# drv.net
KiCad netlist of a schematic drawn in EAGLE
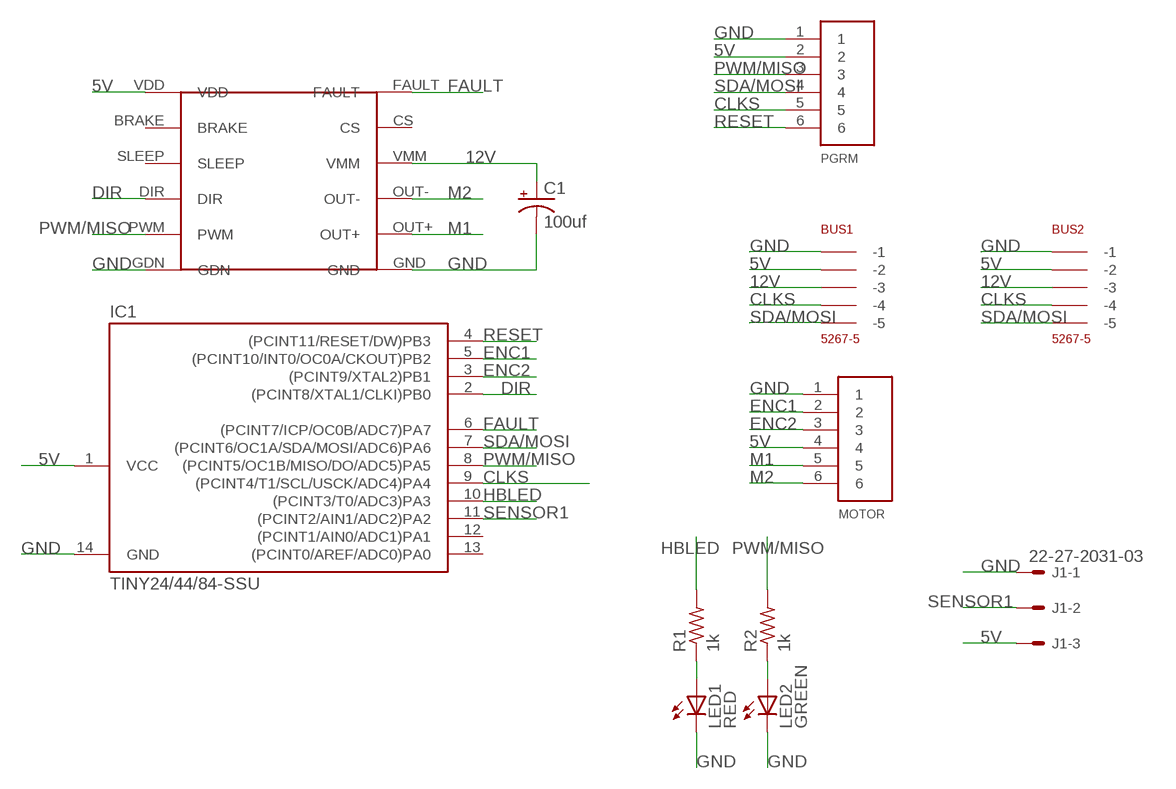
[diagram p0: schematic, sheet 1]

(export (version "E")
  (design (tool "Eeschema 10.0.6"))
  (components
    (comp (ref "BUS1")
      (value "5267-5")
      (footprint "eagle-import:5267-5")
      (libsource (lib "eagle-import") (part "5267-5"))
    )
    (comp (ref "BUS2")
      (value "5267-5")
      (footprint "eagle-import:5267-5")
      (libsource (lib "eagle-import") (part "5267-5"))
    )
    (comp (ref "C1")
      (value "100uf")
      (footprint "eagle-import:E5-10,5")
      (libsource (lib "eagle-import") (part "CPOL-USE5-10.5"))
    )
    (comp (ref "IC1")
      (value "TINY24/44/84-SSU")
      (footprint "eagle-import:SOIC14")
      (libsource (lib "eagle-import") (part "TINY24/44/84-SSU"))
    )
    (comp (ref "J1")
      (value "22-27-2031-03")
      (footprint "eagle-import:6410-03")
      (fields (field (name "MF") "MOLEX"))
      (libsource (lib "eagle-import") (part "22-?-0327-2031"))
    )
    (comp (ref "LED1")
      (value "RED")
      (footprint "eagle-import:1206")
      (libsource (lib "eagle-import") (part "LEDSMT1206"))
    )
    (comp (ref "LED2")
      (value "GREEN")
      (footprint "eagle-import:1206")
      (libsource (lib "eagle-import") (part "LEDSMT1206"))
    )
    (comp (ref "MOTOR")
      (value "6PIN")
      (footprint "eagle-import:B6B-PH-K-S")
      (libsource (lib "eagle-import") (part "6PIN"))
    )
    (comp (ref "PGRM")
      (value "6PIN")
      (footprint "eagle-import:B6B-PH-K-S")
      (libsource (lib "eagle-import") (part "6PIN"))
    )
    (comp (ref "R1")
      (value "1k")
      (footprint "eagle-import:M1206")
      (libsource (lib "eagle-import") (part "R-US_M1206"))
    )
    (comp (ref "R2")
      (value "1k")
      (footprint "eagle-import:M1206")
      (libsource (lib "eagle-import") (part "R-US_M1206"))
    )
    (comp (ref "U$1")
      (value "DRV8801BR")
      (footprint "eagle-import:DRV8801BR")
      (libsource (lib "eagle-import") (part "DRV8801BR"))
    )
  )
  (nets
    (net (code "1") (name "/5V") (class "Default")
      (node (ref "BUS1") (pin "P$2") (pinfunction "-2_P$2") (pintype "bidirectional"))
      (node (ref "BUS2") (pin "P$2") (pinfunction "-2_P$2") (pintype "bidirectional"))
      (node (ref "IC1") (pin "1") (pinfunction "VCC_1") (pintype "power_in"))
      (node (ref "J1") (pin "3") (pinfunction "S_3") (pintype "passive"))
      (node (ref "MOTOR") (pin "4") (pinfunction "4_4") (pintype "bidirectional"))
      (node (ref "PGRM") (pin "2") (pinfunction "2_2") (pintype "bidirectional"))
      (node (ref "U$1") (pin "VDD") (pinfunction "VDD_VDD") (pintype "bidirectional"))
    )
    (net (code "2") (name "/12V") (class "Default")
      (node (ref "BUS1") (pin "P$3") (pinfunction "-3_P$3") (pintype "bidirectional"))
      (node (ref "BUS2") (pin "P$3") (pinfunction "-3_P$3") (pintype "bidirectional"))
      (node (ref "C1") (pin "+") (pinfunction "+_+") (pintype "passive"))
      (node (ref "U$1") (pin "VMM") (pinfunction "VMM_VMM") (pintype "bidirectional"))
    )
    (net (code "3") (name "/CLKS") (class "Default")
      (node (ref "BUS1") (pin "P$4") (pinfunction "-4_P$4") (pintype "bidirectional"))
      (node (ref "BUS2") (pin "P$4") (pinfunction "-4_P$4") (pintype "bidirectional"))
      (node (ref "IC1") (pin "9") (pinfunction "(PCINT4/T1/SCL/USCK/ADC4)PA4_9") (pintype "bidirectional"))
      (node (ref "PGRM") (pin "5") (pinfunction "5_5") (pintype "bidirectional"))
    )
    (net (code "4") (name "/DIR") (class "Default")
      (node (ref "IC1") (pin "2") (pinfunction "(PCINT8/XTAL1/CLKI)PB0_2") (pintype "bidirectional"))
      (node (ref "U$1") (pin "DIR") (pinfunction "DIR_DIR") (pintype "bidirectional"))
    )
    (net (code "5") (name "/ENC1") (class "Default")
      (node (ref "IC1") (pin "5") (pinfunction "(PCINT10/INT0/OC0A/CKOUT)PB2_5") (pintype "bidirectional"))
      (node (ref "MOTOR") (pin "2") (pinfunction "2_2") (pintype "bidirectional"))
    )
    (net (code "6") (name "/ENC2") (class "Default")
      (node (ref "IC1") (pin "3") (pinfunction "(PCINT9/XTAL2)PB1_3") (pintype "bidirectional"))
      (node (ref "MOTOR") (pin "3") (pinfunction "3_3") (pintype "bidirectional"))
    )
    (net (code "7") (name "/FAULT") (class "Default")
      (node (ref "IC1") (pin "6") (pinfunction "(PCINT7/ICP/OC0B/ADC7)PA7_6") (pintype "bidirectional"))
      (node (ref "U$1") (pin "FAULT") (pinfunction "FAULT_FAULT") (pintype "bidirectional"))
    )
    (net (code "8") (name "/GND") (class "Default")
      (node (ref "BUS1") (pin "P$1") (pinfunction "-1_P$1") (pintype "bidirectional"))
      (node (ref "BUS2") (pin "P$1") (pinfunction "-1_P$1") (pintype "bidirectional"))
      (node (ref "C1") (pin "-") (pinfunction "-_-") (pintype "passive"))
      (node (ref "IC1") (pin "14") (pinfunction "GND_14") (pintype "power_in"))
      (node (ref "J1") (pin "1") (pinfunction "S_1") (pintype "passive"))
      (node (ref "LED1") (pin "C") (pinfunction "C_C") (pintype "passive"))
      (node (ref "LED2") (pin "C") (pinfunction "C_C") (pintype "passive"))
      (node (ref "MOTOR") (pin "1") (pinfunction "1_1") (pintype "bidirectional"))
      (node (ref "PGRM") (pin "1") (pinfunction "1_1") (pintype "bidirectional"))
      (node (ref "U$1") (pin "GDN") (pinfunction "GDN_GDN") (pintype "bidirectional"))
      (node (ref "U$1") (pin "GND") (pinfunction "GND_GND") (pintype "bidirectional"))
    )
    (net (code "9") (name "/HBLED") (class "Default")
      (node (ref "IC1") (pin "10") (pinfunction "(PCINT3/T0/ADC3)PA3_10") (pintype "bidirectional"))
      (node (ref "R1") (pin "2") (pinfunction "2_2") (pintype "passive"))
    )
    (net (code "10") (name "/M1") (class "Default")
      (node (ref "MOTOR") (pin "5") (pinfunction "5_5") (pintype "bidirectional"))
      (node (ref "U$1") (pin "OUT+") (pinfunction "OUT+_OUT+") (pintype "bidirectional"))
    )
    (net (code "11") (name "/M2") (class "Default")
      (node (ref "MOTOR") (pin "6") (pinfunction "6_6") (pintype "bidirectional"))
      (node (ref "U$1") (pin "OUT-") (pinfunction "OUT-_OUT-") (pintype "bidirectional"))
    )
    (net (code "12") (name "/PWM{slash}MISO") (class "Default")
      (node (ref "IC1") (pin "8") (pinfunction "(PCINT5/OC1B/MISO/DO/ADC5)PA5_8") (pintype "bidirectional"))
      (node (ref "PGRM") (pin "3") (pinfunction "3_3") (pintype "bidirectional"))
      (node (ref "R2") (pin "2") (pinfunction "2_2") (pintype "passive"))
      (node (ref "U$1") (pin "PWM") (pinfunction "PWM_PWM") (pintype "bidirectional"))
    )
    (net (code "13") (name "/RESET") (class "Default")
      (node (ref "IC1") (pin "4") (pinfunction "(PCINT11/RESET/DW)PB3_4") (pintype "bidirectional"))
      (node (ref "PGRM") (pin "6") (pinfunction "6_6") (pintype "bidirectional"))
    )
    (net (code "14") (name "/SDA{slash}MOSI") (class "Default")
      (node (ref "BUS1") (pin "P$5") (pinfunction "-5_P$5") (pintype "bidirectional"))
      (node (ref "BUS2") (pin "P$5") (pinfunction "-5_P$5") (pintype "bidirectional"))
      (node (ref "IC1") (pin "7") (pinfunction "(PCINT6/OC1A/SDA/MOSI/ADC6)PA6_7") (pintype "bidirectional"))
      (node (ref "PGRM") (pin "4") (pinfunction "4_4") (pintype "bidirectional"))
    )
    (net (code "15") (name "/SENSOR1") (class "Default")
      (node (ref "IC1") (pin "11") (pinfunction "(PCINT2/AIN1/ADC2)PA2_11") (pintype "bidirectional"))
      (node (ref "J1") (pin "2") (pinfunction "S_2") (pintype "passive"))
    )
    (net (code "16") (name "Net-(LED1-PadA)") (class "Default")
      (node (ref "LED1") (pin "A") (pinfunction "A_A") (pintype "passive"))
      (node (ref "R1") (pin "1") (pinfunction "1_1") (pintype "passive"))
    )
    (net (code "17") (name "Net-(LED2-PadA)") (class "Default")
      (node (ref "LED2") (pin "A") (pinfunction "A_A") (pintype "passive"))
      (node (ref "R2") (pin "1") (pinfunction "1_1") (pintype "passive"))
    )
    (net (code "18") (name "unconnected-(IC1-(PCINT0{slash}AREF{slash}ADC0)PA0-Pad13)") (class "Default")
      (node (ref "IC1") (pin "13") (pinfunction "(PCINT0/AREF/ADC0)PA0_13") (pintype "bidirectional"))
    )
    (net (code "19") (name "unconnected-(IC1-(PCINT1{slash}AIN0{slash}ADC1)PA1-Pad12)") (class "Default")
      (node (ref "IC1") (pin "12") (pinfunction "(PCINT1/AIN0/ADC1)PA1_12") (pintype "bidirectional"))
    )
    (net (code "20") (name "unconnected-(U$1-PadBRAKE)") (class "Default")
      (node (ref "U$1") (pin "BRAKE") (pinfunction "BRAKE_BRAKE") (pintype "bidirectional"))
    )
    (net (code "21") (name "unconnected-(U$1-PadCS)") (class "Default")
      (node (ref "U$1") (pin "CS") (pinfunction "CS_CS") (pintype "bidirectional"))
    )
    (net (code "22") (name "unconnected-(U$1-PadSLEEP)") (class "Default")
      (node (ref "U$1") (pin "SLEEP") (pinfunction "SLEEP_SLEEP") (pintype "bidirectional"))
    )
  )
)
